# Touch_Sensor_Address.net
KiCad netlist of a schematic drawn in Altium Designer
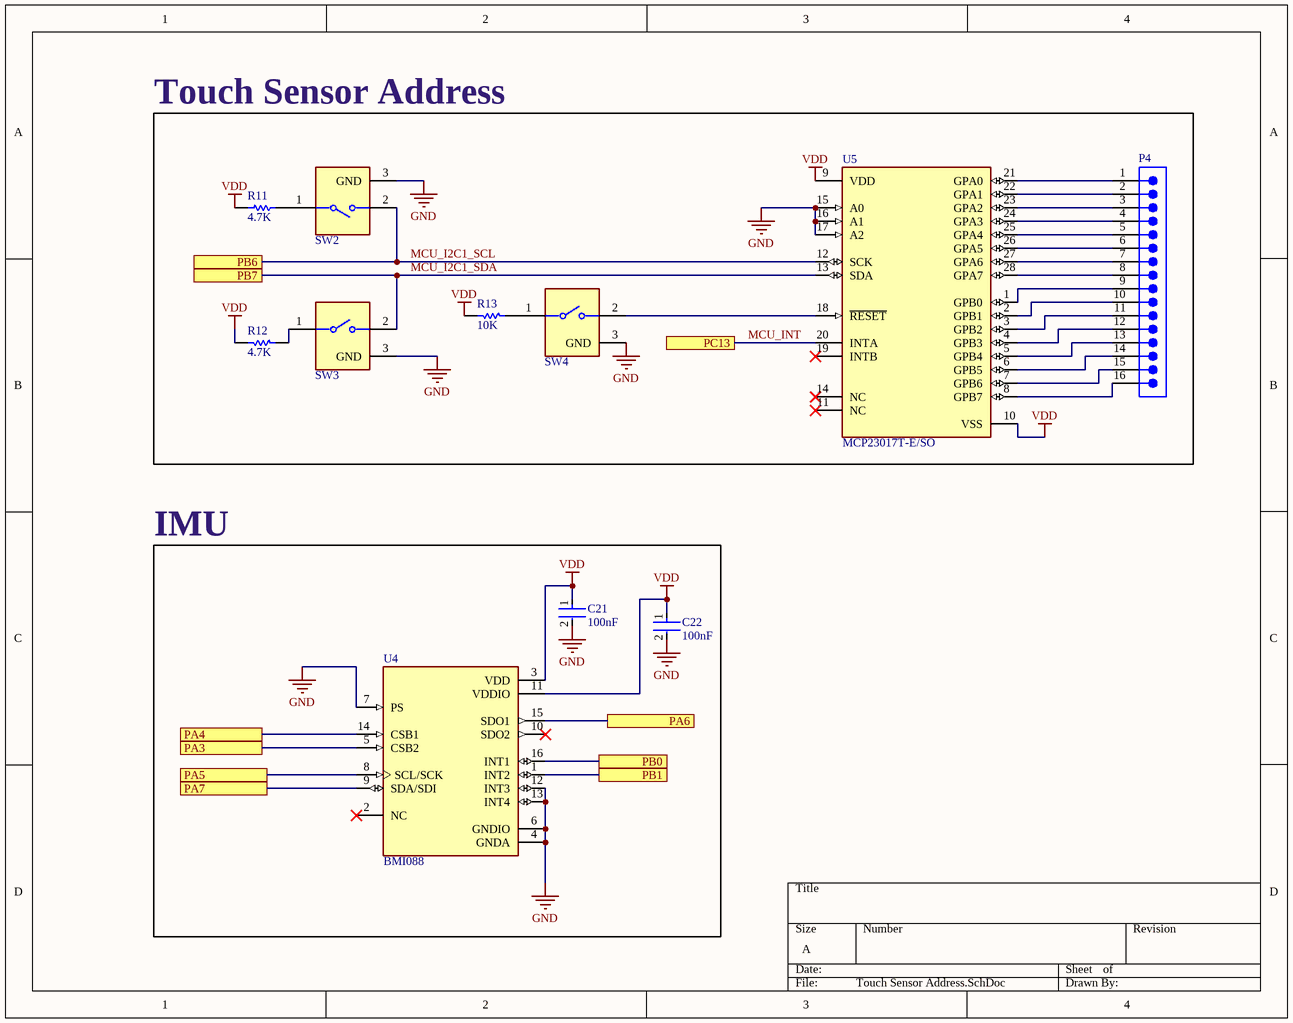
[diagram p0: Touch Sensor Address.SchDoc]

(export (version "E")
  (design (tool "Eeschema 10.0.6"))
  (components
    (comp (ref "C21")
      (value "100nF")
      (footprint "FP-CL93-IPC_C")
      (description "Cap Ceramic 100nF 10V X7R ±10% SMD 0402 +125°C Paper T/R")
      (libsource (lib "Altium Content Vault") (part "b4654b650e69147ec39a6b967a45e02"))
    )
    (comp (ref "C22")
      (value "100nF")
      (footprint "FP-CL93-IPC_C")
      (description "Cap Ceramic 100nF 10V X7R ±10% SMD 0402 +125°C Paper T/R")
      (libsource (lib "Altium Content Vault") (part "b4654b650e69147ec39a6b967a45e02"))
    )
    (comp (ref "P4")
      (value "61301611121")
      (footprint "61301611121")
      (libsource (lib "Altium Content Vault") (part "Header_Male_1R_16P"))
    )
    (comp (ref "R11")
      (value "4.7K")
      (footprint "RESC1608X55X25LL10T15")
      (description "Chip Resistor, 4.7 KOhm, +/- 1%, 0.1 W, -55 to 155 degC, 0603 (1608 Metric), RoHS, Tape and Reel")
      (fields (field (name "MANUFACTURER") "Yageo") (field (name "TOLERANCE") "1%"))
      (libsource (lib "Altium Content Vault") (part "RES-2"))
    )
    (comp (ref "R12")
      (value "4.7K")
      (footprint "RESC1608X55X25LL10T15")
      (description "Chip Resistor, 4.7 KOhm, +/- 1%, 0.1 W, -55 to 155 degC, 0603 (1608 Metric), RoHS, Tape and Reel")
      (fields (field (name "MANUFACTURER") "Yageo") (field (name "TOLERANCE") "1%"))
      (libsource (lib "Altium Content Vault") (part "RES-2"))
    )
    (comp (ref "R13")
      (value "10K")
      (footprint "RESC1608X55X25ML10T15")
      (description "Resistor, 10 KOhm, +/- 5%, 100 mW, -55 to 155 degC, 0603 (1608 Metric), RoHS, Tape and Reel")
      (fields (field (name "MANUFACTURER") "Yageo") (field (name "TOLERANCE") "5%"))
      (libsource (lib "Altium Content Vault") (part "RES-2"))
    )
    (comp (ref "SW2")
      (value "B3U-1100PM")
      (footprint "FP-B3U-1100PM-MFG")
      (description "SWITCH TACTILE SPST-NO 0.05A 12V")
      (libsource (lib "") (part "6d7322ea62e06c21cb959ab9578dfa0_1"))
    )
    (comp (ref "SW3")
      (value "B3U-1100PM")
      (footprint "FP-B3U-1100PM-MFG")
      (description "SWITCH TACTILE SPST-NO 0.05A 12V")
      (libsource (lib "Altium Content Vault") (part "6d7322ea62e06c21cb959ab9578dfa0"))
    )
    (comp (ref "SW4")
      (value "B3U-1100PM")
      (footprint "FP-B3U-1100PM-MFG")
      (description "SWITCH TACTILE SPST-NO 0.05A 12V")
      (libsource (lib "Altium Content Vault") (part "6d7322ea62e06c21cb959ab9578dfa0"))
    )
    (comp (ref "U4")
      (value "BMI088")
      (footprint "PQFN50P450X300X100-16N")
      (libsource (lib "BMI088") (part "BMI088"))
    )
    (comp (ref "U5")
      (value "MCP23017T-E/SO")
      (footprint "FP-C04-052-MFG")
      (description "IC I/O EXPANDER I2C 16B 28SOIC")
      (libsource (lib "Altium Content Vault") (part "5a9070f3ac31e52c3c9f34e69183557"))
    )
  )
  (nets
    (net (code "1") (name "/MCU_I2C1_SCL") (class "Default")
      (node (ref "SW2") (pin "2") (pinfunction "2_2") (pintype "passive"))
      (node (ref "U5") (pin "12") (pinfunction "SCK_12") (pintype "bidirectional"))
    )
    (net (code "2") (name "/MCU_I2C1_SDA") (class "Default")
      (node (ref "SW3") (pin "2") (pinfunction "2_2") (pintype "passive"))
      (node (ref "U5") (pin "13") (pinfunction "SDA_13") (pintype "bidirectional"))
    )
    (net (code "3") (name "/MCU_INT") (class "Default")
      (node (ref "U5") (pin "20") (pinfunction "INTA_20") (pintype "open_collector"))
    )
    (net (code "4") (name "/PA3") (class "Default")
      (node (ref "U4") (pin "5") (pinfunction "CSB2_5") (pintype "input"))
    )
    (net (code "5") (name "/PA4") (class "Default")
      (node (ref "U4") (pin "14") (pinfunction "CSB1_14") (pintype "input"))
    )
    (net (code "6") (name "/PA5") (class "Default")
      (node (ref "U4") (pin "8") (pinfunction "SCL/SCK_8") (pintype "input"))
    )
    (net (code "7") (name "/PA6") (class "Default")
      (node (ref "U4") (pin "15") (pinfunction "SDO1_15") (pintype "output"))
    )
    (net (code "8") (name "/PA7") (class "Default")
      (node (ref "U4") (pin "9") (pinfunction "SDA/SDI_9") (pintype "bidirectional"))
    )
    (net (code "9") (name "/PB0") (class "Default")
      (node (ref "U4") (pin "16") (pinfunction "INT1_16") (pintype "bidirectional"))
    )
    (net (code "10") (name "/PB1") (class "Default")
      (node (ref "U4") (pin "1") (pinfunction "INT2_1") (pintype "bidirectional"))
    )
    (net (code "11") (name "GND") (class "Default")
      (node (ref "C21") (pin "2") (pinfunction "2_2") (pintype "passive"))
      (node (ref "C22") (pin "2") (pinfunction "2_2") (pintype "passive"))
      (node (ref "SW2") (pin "3") (pinfunction "GND_3") (pintype "power_in"))
      (node (ref "SW3") (pin "3") (pinfunction "GND_3") (pintype "power_in"))
      (node (ref "SW4") (pin "3") (pinfunction "GND_3") (pintype "power_in"))
      (node (ref "U4") (pin "12") (pinfunction "INT3_12") (pintype "bidirectional"))
      (node (ref "U4") (pin "13") (pinfunction "INT4_13") (pintype "bidirectional"))
      (node (ref "U4") (pin "4") (pinfunction "GNDA_4") (pintype "power_in"))
      (node (ref "U4") (pin "6") (pinfunction "GNDIO_6") (pintype "power_in"))
      (node (ref "U4") (pin "7") (pinfunction "PS_7") (pintype "input"))
      (node (ref "U5") (pin "15") (pinfunction "A0_15") (pintype "input"))
      (node (ref "U5") (pin "16") (pinfunction "A1_16") (pintype "input"))
      (node (ref "U5") (pin "17") (pinfunction "A2_17") (pintype "input"))
    )
    (net (code "12") (name "Net-(R11-Pad2)") (class "Default")
      (node (ref "R11") (pin "2") (pinfunction "2_2") (pintype "passive"))
      (node (ref "SW2") (pin "1") (pinfunction "1_1") (pintype "passive"))
    )
    (net (code "13") (name "Net-(R12-Pad2)") (class "Default")
      (node (ref "R12") (pin "2") (pinfunction "2_2") (pintype "passive"))
      (node (ref "SW3") (pin "1") (pinfunction "1_1") (pintype "passive"))
    )
    (net (code "14") (name "Net-(R13-Pad2)") (class "Default")
      (node (ref "R13") (pin "2") (pinfunction "2_2") (pintype "passive"))
      (node (ref "SW4") (pin "1") (pinfunction "1_1") (pintype "passive"))
    )
    (net (code "15") (name "Net-(U5-GPA0)") (class "Default")
      (node (ref "P4") (pin "1") (pinfunction "1_1") (pintype "passive"))
      (node (ref "U5") (pin "21") (pinfunction "GPA0_21") (pintype "bidirectional"))
    )
    (net (code "16") (name "Net-(U5-GPA1)") (class "Default")
      (node (ref "P4") (pin "2") (pinfunction "2_2") (pintype "passive"))
      (node (ref "U5") (pin "22") (pinfunction "GPA1_22") (pintype "bidirectional"))
    )
    (net (code "17") (name "Net-(U5-GPA2)") (class "Default")
      (node (ref "P4") (pin "3") (pinfunction "3_3") (pintype "passive"))
      (node (ref "U5") (pin "23") (pinfunction "GPA2_23") (pintype "bidirectional"))
    )
    (net (code "18") (name "Net-(U5-GPA3)") (class "Default")
      (node (ref "P4") (pin "4") (pinfunction "4_4") (pintype "passive"))
      (node (ref "U5") (pin "24") (pinfunction "GPA3_24") (pintype "bidirectional"))
    )
    (net (code "19") (name "Net-(U5-GPA4)") (class "Default")
      (node (ref "P4") (pin "5") (pinfunction "5_5") (pintype "passive"))
      (node (ref "U5") (pin "25") (pinfunction "GPA4_25") (pintype "bidirectional"))
    )
    (net (code "20") (name "Net-(U5-GPA5)") (class "Default")
      (node (ref "P4") (pin "6") (pinfunction "6_6") (pintype "passive"))
      (node (ref "U5") (pin "26") (pinfunction "GPA5_26") (pintype "bidirectional"))
    )
    (net (code "21") (name "Net-(U5-GPA6)") (class "Default")
      (node (ref "P4") (pin "7") (pinfunction "7_7") (pintype "passive"))
      (node (ref "U5") (pin "27") (pinfunction "GPA6_27") (pintype "bidirectional"))
    )
    (net (code "22") (name "Net-(U5-GPA7)") (class "Default")
      (node (ref "P4") (pin "8") (pinfunction "8_8") (pintype "passive"))
      (node (ref "U5") (pin "28") (pinfunction "GPA7_28") (pintype "bidirectional"))
    )
    (net (code "23") (name "Net-(U5-GPB0)") (class "Default")
      (node (ref "P4") (pin "9") (pinfunction "9_9") (pintype "passive"))
      (node (ref "U5") (pin "1") (pinfunction "GPB0_1") (pintype "bidirectional"))
    )
    (net (code "24") (name "Net-(U5-GPB1)") (class "Default")
      (node (ref "P4") (pin "10") (pinfunction "10_10") (pintype "passive"))
      (node (ref "U5") (pin "2") (pinfunction "GPB1_2") (pintype "bidirectional"))
    )
    (net (code "25") (name "Net-(U5-GPB2)") (class "Default")
      (node (ref "P4") (pin "11") (pinfunction "11_11") (pintype "passive"))
      (node (ref "U5") (pin "3") (pinfunction "GPB2_3") (pintype "bidirectional"))
    )
    (net (code "26") (name "Net-(U5-GPB3)") (class "Default")
      (node (ref "P4") (pin "12") (pinfunction "12_12") (pintype "passive"))
      (node (ref "U5") (pin "4") (pinfunction "GPB3_4") (pintype "bidirectional"))
    )
    (net (code "27") (name "Net-(U5-GPB4)") (class "Default")
      (node (ref "P4") (pin "13") (pinfunction "13_13") (pintype "passive"))
      (node (ref "U5") (pin "5") (pinfunction "GPB4_5") (pintype "bidirectional"))
    )
    (net (code "28") (name "Net-(U5-GPB5)") (class "Default")
      (node (ref "P4") (pin "14") (pinfunction "14_14") (pintype "passive"))
      (node (ref "U5") (pin "6") (pinfunction "GPB5_6") (pintype "bidirectional"))
    )
    (net (code "29") (name "Net-(U5-GPB6)") (class "Default")
      (node (ref "P4") (pin "15") (pinfunction "15_15") (pintype "passive"))
      (node (ref "U5") (pin "7") (pinfunction "GPB6_7") (pintype "bidirectional"))
    )
    (net (code "30") (name "Net-(U5-GPB7)") (class "Default")
      (node (ref "P4") (pin "16") (pinfunction "16_16") (pintype "passive"))
      (node (ref "U5") (pin "8") (pinfunction "GPB7_8") (pintype "bidirectional"))
    )
    (net (code "31") (name "Net-(U5-~{RESET})") (class "Default")
      (node (ref "SW4") (pin "2") (pinfunction "2_2") (pintype "passive"))
      (node (ref "U5") (pin "18") (pinfunction "~{RESET}_18") (pintype "input"))
    )
    (net (code "32") (name "VDD") (class "Default")
      (node (ref "C21") (pin "1") (pinfunction "1_1") (pintype "passive"))
      (node (ref "C22") (pin "1") (pinfunction "1_1") (pintype "passive"))
      (node (ref "R11") (pin "1") (pinfunction "1_1") (pintype "passive"))
      (node (ref "R12") (pin "1") (pinfunction "1_1") (pintype "passive"))
      (node (ref "R13") (pin "1") (pinfunction "1_1") (pintype "passive"))
      (node (ref "U4") (pin "11") (pinfunction "VDDIO_11") (pintype "power_in"))
      (node (ref "U4") (pin "3") (pinfunction "VDD_3") (pintype "power_in"))
      (node (ref "U5") (pin "10") (pinfunction "VSS_10") (pintype "power_in"))
      (node (ref "U5") (pin "9") (pinfunction "VDD_9") (pintype "power_in"))
    )
    (net (code "33") (name "unconnected-(U4-NC-Pad2)") (class "Default")
      (node (ref "U4") (pin "2") (pinfunction "NC_2") (pintype "passive+no_connect"))
    )
    (net (code "34") (name "unconnected-(U4-SDO2-Pad10)") (class "Default")
      (node (ref "U4") (pin "10") (pinfunction "SDO2_10") (pintype "output+no_connect"))
    )
    (net (code "35") (name "unconnected-(U5-INTB-Pad19)") (class "Default")
      (node (ref "U5") (pin "19") (pinfunction "INTB_19") (pintype "open_collector+no_connect"))
    )
    (net (code "36") (name "unconnected-(U5-NC-Pad11)") (class "Default")
      (node (ref "U5") (pin "11") (pinfunction "NC_11") (pintype "passive+no_connect"))
    )
    (net (code "37") (name "unconnected-(U5-NC-Pad14)") (class "Default")
      (node (ref "U5") (pin "14") (pinfunction "NC_14") (pintype "passive+no_connect"))
    )
  )
)
